# schematic.net
KiCad netlist of a schematic drawn in EAGLE
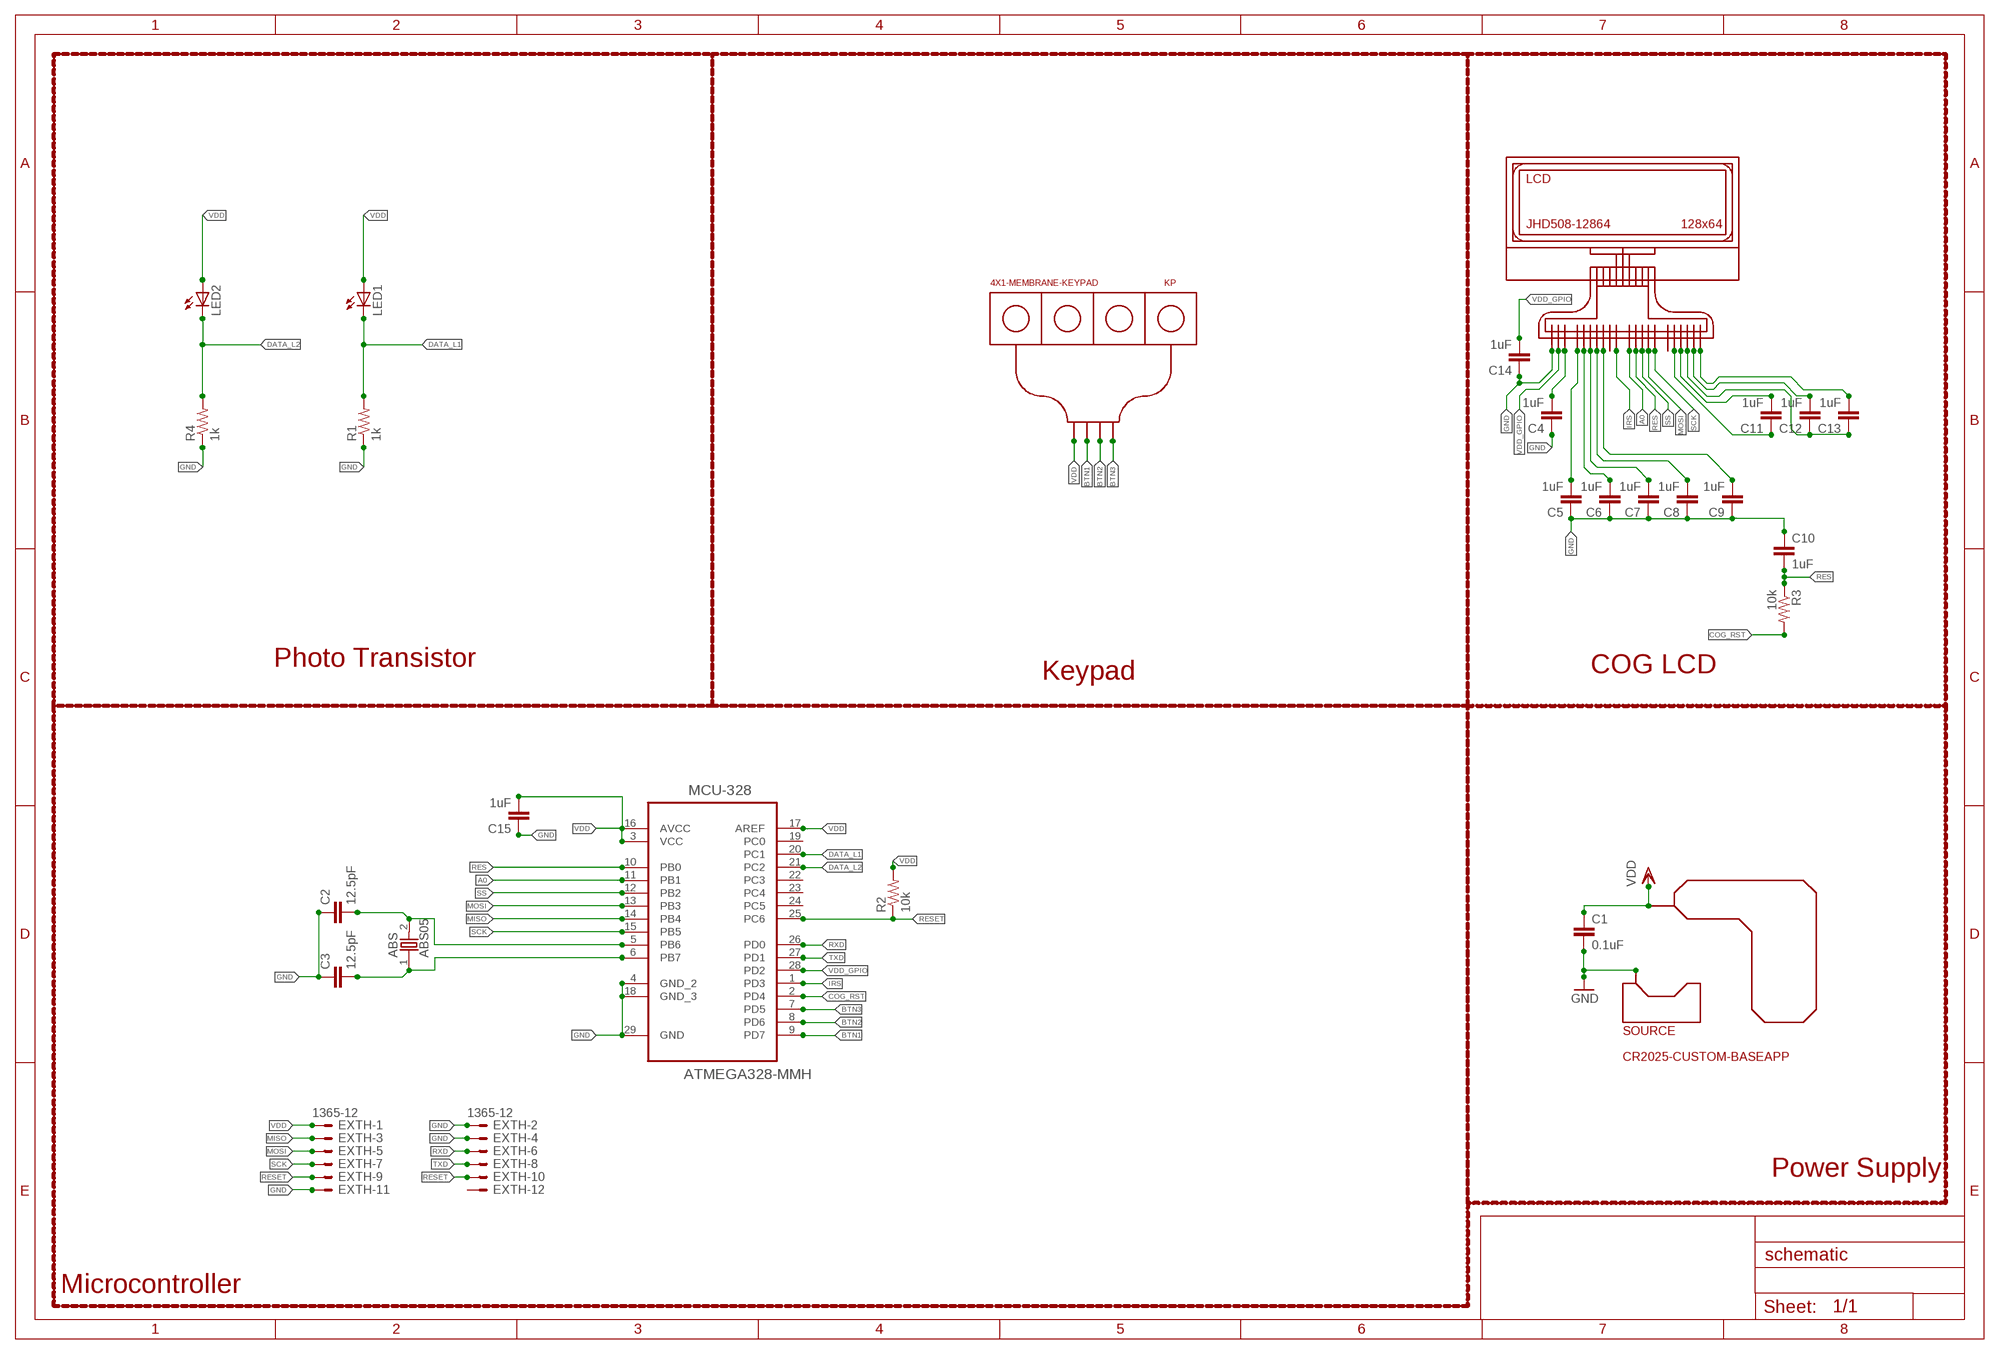
[diagram p0: schematic, sheet 1]

(export (version "E")
  (design (tool "Eeschema 10.0.6"))
  (components
    (comp (ref "ABS")
      (value "ABS05")
      (footprint "eagle-import:ABS05")
      (libsource (lib "eagle-import") (part "ABS05"))
    )
    (comp (ref "C1")
      (value "0.1uF")
      (footprint "eagle-import:0402-CAP")
      (libsource (lib "eagle-import") (part "CAP0402-CAP"))
    )
    (comp (ref "C2")
      (value "12.5pF")
      (footprint "eagle-import:0402-CAP")
      (libsource (lib "eagle-import") (part "CAP0402-CAP"))
    )
    (comp (ref "C3")
      (value "12.5pF")
      (footprint "eagle-import:0402-CAP")
      (libsource (lib "eagle-import") (part "CAP0402-CAP"))
    )
    (comp (ref "C4")
      (value "1uF")
      (footprint "eagle-import:0402-CAP")
      (libsource (lib "eagle-import") (part "CAP0402-CAP"))
    )
    (comp (ref "C5")
      (value "1uF")
      (footprint "eagle-import:0402-CAP")
      (libsource (lib "eagle-import") (part "CAP0402-CAP"))
    )
    (comp (ref "C6")
      (value "1uF")
      (footprint "eagle-import:0402-CAP")
      (libsource (lib "eagle-import") (part "CAP0402-CAP"))
    )
    (comp (ref "C7")
      (value "1uF")
      (footprint "eagle-import:0402-CAP")
      (libsource (lib "eagle-import") (part "CAP0402-CAP"))
    )
    (comp (ref "C8")
      (value "1uF")
      (footprint "eagle-import:0402-CAP")
      (libsource (lib "eagle-import") (part "CAP0402-CAP"))
    )
    (comp (ref "C9")
      (value "1uF")
      (footprint "eagle-import:0402-CAP")
      (libsource (lib "eagle-import") (part "CAP0402-CAP"))
    )
    (comp (ref "C10")
      (value "1uF")
      (footprint "eagle-import:0402-CAP")
      (libsource (lib "eagle-import") (part "CAP0402-CAP"))
    )
    (comp (ref "C11")
      (value "1uF")
      (footprint "eagle-import:0402-CAP")
      (libsource (lib "eagle-import") (part "CAP0402-CAP"))
    )
    (comp (ref "C12")
      (value "1uF")
      (footprint "eagle-import:0402-CAP")
      (libsource (lib "eagle-import") (part "CAP0402-CAP"))
    )
    (comp (ref "C13")
      (value "1uF")
      (footprint "eagle-import:0402-CAP")
      (libsource (lib "eagle-import") (part "CAP0402-CAP"))
    )
    (comp (ref "C14")
      (value "1uF")
      (footprint "eagle-import:0402-CAP")
      (libsource (lib "eagle-import") (part "CAP0402-CAP"))
    )
    (comp (ref "C15")
      (value "1uF")
      (footprint "eagle-import:0402-CAP")
      (libsource (lib "eagle-import") (part "CAP0402-CAP"))
    )
    (comp (ref "EXTH")
      (value "1365-12")
      (footprint "eagle-import:1365-12")
      (libsource (lib "eagle-import") (part "1365-12"))
    )
    (comp (ref "KP")
      (value "4X1-MEMBRANE-KEYPAD")
      (footprint "eagle-import:4X1-MEMBRANE-KEYPAD")
      (libsource (lib "eagle-import") (part "4X1-MEMBRANE-KEYPAD"))
    )
    (comp (ref "LCD")
      (value "JHD508-12864")
      (footprint "eagle-import:FSTN")
      (libsource (lib "eagle-import") (part "JHD508-12864"))
    )
    (comp (ref "LED1")
      (value "LEDCHIP-LED0805")
      (footprint "eagle-import:CHIP-LED0805")
      (libsource (lib "eagle-import") (part "LEDCHIP-LED0805"))
    )
    (comp (ref "LED2")
      (value "LEDCHIP-LED0805")
      (footprint "eagle-import:CHIP-LED0805")
      (libsource (lib "eagle-import") (part "LEDCHIP-LED0805"))
    )
    (comp (ref "MCU-328")
      (value "ATMEGA328-MMH")
      (footprint "eagle-import:QFN45P400X400X100-29N")
      (libsource (lib "eagle-import") (part "ATMEGA328-MMH"))
    )
    (comp (ref "R1")
      (value "1k")
      (footprint "eagle-import:0402-RES")
      (libsource (lib "eagle-import") (part "RESISTOR0402-RES"))
    )
    (comp (ref "R2")
      (value "10k")
      (footprint "eagle-import:0402-RES")
      (libsource (lib "eagle-import") (part "RESISTOR0402-RES"))
    )
    (comp (ref "R3")
      (value "10k")
      (footprint "eagle-import:0402-RES")
      (libsource (lib "eagle-import") (part "RESISTOR0402-RES"))
    )
    (comp (ref "R4")
      (value "1k")
      (footprint "eagle-import:0402-RES")
      (libsource (lib "eagle-import") (part "RESISTOR0402-RES"))
    )
    (comp (ref "SOURCE")
      (value "CR2025-CUSTOM-BASEAPP")
      (footprint "eagle-import:CR2025-CUSTOM-BASEAPP")
      (libsource (lib "eagle-import") (part "CR2025-CUSTOM-BASEAPP"))
    )
  )
  (nets
    (net (code "1") (name "A0") (class "Default")
      (node (ref "LCD") (pin "P$19") (pinfunction "A0_P$19") (pintype "bidirectional"))
      (node (ref "MCU-328") (pin "11") (pinfunction "PB1_11") (pintype "bidirectional"))
    )
    (net (code "2") (name "BTN1") (class "Default")
      (node (ref "KP") (pin "P$2") (pinfunction "P$2_P$2") (pintype "bidirectional"))
      (node (ref "MCU-328") (pin "9") (pinfunction "PD7_9") (pintype "bidirectional"))
    )
    (net (code "3") (name "BTN2") (class "Default")
      (node (ref "KP") (pin "P$3") (pinfunction "P$3_P$3") (pintype "bidirectional"))
      (node (ref "MCU-328") (pin "8") (pinfunction "PD6_8") (pintype "bidirectional"))
    )
    (net (code "4") (name "BTN3") (class "Default")
      (node (ref "KP") (pin "P$4") (pinfunction "P$4_P$4") (pintype "bidirectional"))
      (node (ref "MCU-328") (pin "7") (pinfunction "PD5_7") (pintype "bidirectional"))
    )
    (net (code "5") (name "COG_RST") (class "Default")
      (node (ref "MCU-328") (pin "2") (pinfunction "PD4_2") (pintype "bidirectional"))
      (node (ref "R3") (pin "2") (pinfunction "2_2") (pintype "passive"))
    )
    (net (code "6") (name "DATA_L1") (class "Default")
      (node (ref "LED1") (pin "C") (pinfunction "C_C") (pintype "passive"))
      (node (ref "MCU-328") (pin "20") (pinfunction "PC1_20") (pintype "bidirectional"))
      (node (ref "R1") (pin "2") (pinfunction "2_2") (pintype "passive"))
    )
    (net (code "7") (name "DATA_L2") (class "Default")
      (node (ref "LED2") (pin "C") (pinfunction "C_C") (pintype "passive"))
      (node (ref "MCU-328") (pin "21") (pinfunction "PC2_21") (pintype "bidirectional"))
      (node (ref "R4") (pin "2") (pinfunction "2_2") (pintype "passive"))
    )
    (net (code "8") (name "GND") (class "Default")
      (node (ref "C1") (pin "2") (pinfunction "2_2") (pintype "passive"))
      (node (ref "C10") (pin "1") (pinfunction "1_1") (pintype "passive"))
      (node (ref "C14") (pin "1") (pinfunction "1_1") (pintype "passive"))
      (node (ref "C15") (pin "1") (pinfunction "1_1") (pintype "passive"))
      (node (ref "C2") (pin "1") (pinfunction "1_1") (pintype "passive"))
      (node (ref "C3") (pin "1") (pinfunction "1_1") (pintype "passive"))
      (node (ref "C4") (pin "1") (pinfunction "1_1") (pintype "passive"))
      (node (ref "C5") (pin "1") (pinfunction "1_1") (pintype "passive"))
      (node (ref "C6") (pin "1") (pinfunction "1_1") (pintype "passive"))
      (node (ref "C7") (pin "1") (pinfunction "1_1") (pintype "passive"))
      (node (ref "C8") (pin "1") (pinfunction "1_1") (pintype "passive"))
      (node (ref "C9") (pin "1") (pinfunction "1_1") (pintype "passive"))
      (node (ref "EXTH") (pin "11") (pinfunction "S_11") (pintype "passive"))
      (node (ref "EXTH") (pin "2") (pinfunction "S_2") (pintype "passive"))
      (node (ref "EXTH") (pin "4") (pinfunction "S_4") (pintype "passive"))
      (node (ref "LCD") (pin "P$15") (pinfunction "GND_P$15") (pintype "bidirectional"))
      (node (ref "MCU-328") (pin "18") (pinfunction "GND_3_18") (pintype "power_in"))
      (node (ref "MCU-328") (pin "29") (pinfunction "GND_29") (pintype "power_in"))
      (node (ref "MCU-328") (pin "4") (pinfunction "GND_2_4") (pintype "power_in"))
      (node (ref "R1") (pin "1") (pinfunction "1_1") (pintype "passive"))
      (node (ref "R4") (pin "1") (pinfunction "1_1") (pintype "passive"))
      (node (ref "SOURCE") (pin "1") (pinfunction "GND_1") (pintype "bidirectional"))
    )
    (net (code "9") (name "IRS") (class "Default")
      (node (ref "LCD") (pin "P$1") (pinfunction "IRS_P$1") (pintype "bidirectional"))
      (node (ref "MCU-328") (pin "1") (pinfunction "PD3_1") (pintype "bidirectional"))
    )
    (net (code "10") (name "MISO") (class "Default")
      (node (ref "EXTH") (pin "3") (pinfunction "S_3") (pintype "passive"))
      (node (ref "MCU-328") (pin "14") (pinfunction "PB4_14") (pintype "bidirectional"))
    )
    (net (code "11") (name "MOSI") (class "Default")
      (node (ref "EXTH") (pin "5") (pinfunction "S_5") (pintype "passive"))
      (node (ref "LCD") (pin "P$17") (pinfunction "SI_P$17") (pintype "bidirectional"))
      (node (ref "MCU-328") (pin "13") (pinfunction "PB3_13") (pintype "bidirectional"))
    )
    (net (code "12") (name "Net-(LCD-CAP1N)") (class "Default")
      (node (ref "C12") (pin "1") (pinfunction "1_1") (pintype "passive"))
      (node (ref "C13") (pin "1") (pinfunction "1_1") (pintype "passive"))
      (node (ref "LCD") (pin "P$11") (pinfunction "CAP1N_P$11") (pintype "bidirectional"))
    )
    (net (code "13") (name "Net-(LCD-CAP1P)") (class "Default")
      (node (ref "C12") (pin "2") (pinfunction "2_2") (pintype "passive"))
      (node (ref "LCD") (pin "P$12") (pinfunction "CAP1P_P$12") (pintype "bidirectional"))
    )
    (net (code "14") (name "Net-(LCD-CAP2N)") (class "Default")
      (node (ref "C11") (pin "2") (pinfunction "2_2") (pintype "passive"))
      (node (ref "LCD") (pin "P$10") (pinfunction "CAP2N_P$10") (pintype "bidirectional"))
    )
    (net (code "15") (name "Net-(LCD-CAP2P)") (class "Default")
      (node (ref "C11") (pin "1") (pinfunction "1_1") (pintype "passive"))
      (node (ref "LCD") (pin "P$9") (pinfunction "CAP2P_P$9") (pintype "bidirectional"))
    )
    (net (code "16") (name "Net-(LCD-CAP3N)") (class "Default")
      (node (ref "C13") (pin "2") (pinfunction "2_2") (pintype "passive"))
      (node (ref "LCD") (pin "P$13") (pinfunction "CAP3N_P$13") (pintype "bidirectional"))
    )
    (net (code "17") (name "Net-(LCD-V1)") (class "Default")
      (node (ref "C5") (pin "2") (pinfunction "2_2") (pintype "passive"))
      (node (ref "LCD") (pin "P$7") (pinfunction "V1_P$7") (pintype "bidirectional"))
    )
    (net (code "18") (name "Net-(LCD-V2)") (class "Default")
      (node (ref "C6") (pin "2") (pinfunction "2_2") (pintype "passive"))
      (node (ref "LCD") (pin "P$6") (pinfunction "V2_P$6") (pintype "bidirectional"))
    )
    (net (code "19") (name "Net-(LCD-V3)") (class "Default")
      (node (ref "C7") (pin "2") (pinfunction "2_2") (pintype "passive"))
      (node (ref "LCD") (pin "P$5") (pinfunction "V3_P$5") (pintype "bidirectional"))
    )
    (net (code "20") (name "Net-(LCD-V4)") (class "Default")
      (node (ref "C8") (pin "2") (pinfunction "2_2") (pintype "passive"))
      (node (ref "LCD") (pin "P$4") (pinfunction "V4_P$4") (pintype "bidirectional"))
    )
    (net (code "21") (name "Net-(LCD-V5)") (class "Default")
      (node (ref "C9") (pin "2") (pinfunction "2_2") (pintype "passive"))
      (node (ref "LCD") (pin "P$3") (pinfunction "V5_P$3") (pintype "bidirectional"))
    )
    (net (code "22") (name "Net-(LCD-VOUT)") (class "Default")
      (node (ref "C4") (pin "2") (pinfunction "2_2") (pintype "passive"))
      (node (ref "LCD") (pin "P$14") (pinfunction "VOUT_P$14") (pintype "bidirectional"))
    )
    (net (code "23") (name "Net-(MCU-328-PB6)") (class "Default")
      (node (ref "ABS") (pin "2") (pinfunction "2_2") (pintype "passive"))
      (node (ref "C2") (pin "2") (pinfunction "2_2") (pintype "passive"))
      (node (ref "MCU-328") (pin "5") (pinfunction "PB6_5") (pintype "bidirectional"))
    )
    (net (code "24") (name "Net-(MCU-328-PB7)") (class "Default")
      (node (ref "ABS") (pin "1") (pinfunction "1_1") (pintype "passive"))
      (node (ref "C3") (pin "2") (pinfunction "2_2") (pintype "passive"))
      (node (ref "MCU-328") (pin "6") (pinfunction "PB7_6") (pintype "bidirectional"))
    )
    (net (code "25") (name "RES") (class "Default")
      (node (ref "C10") (pin "2") (pinfunction "2_2") (pintype "passive"))
      (node (ref "LCD") (pin "P$20") (pinfunction "/RES_P$20") (pintype "bidirectional"))
      (node (ref "MCU-328") (pin "10") (pinfunction "PB0_10") (pintype "bidirectional"))
      (node (ref "R3") (pin "1") (pinfunction "1_1") (pintype "passive"))
    )
    (net (code "26") (name "RESET") (class "Default")
      (node (ref "EXTH") (pin "10") (pinfunction "S_10") (pintype "passive"))
      (node (ref "EXTH") (pin "9") (pinfunction "S_9") (pintype "passive"))
      (node (ref "MCU-328") (pin "25") (pinfunction "PC6_25") (pintype "bidirectional"))
      (node (ref "R2") (pin "1") (pinfunction "1_1") (pintype "passive"))
    )
    (net (code "27") (name "RXD") (class "Default")
      (node (ref "EXTH") (pin "6") (pinfunction "S_6") (pintype "passive"))
      (node (ref "MCU-328") (pin "26") (pinfunction "PD0_26") (pintype "bidirectional"))
    )
    (net (code "28") (name "SCK") (class "Default")
      (node (ref "EXTH") (pin "7") (pinfunction "S_7") (pintype "passive"))
      (node (ref "LCD") (pin "P$18") (pinfunction "SCL_P$18") (pintype "bidirectional"))
      (node (ref "MCU-328") (pin "15") (pinfunction "PB5_15") (pintype "bidirectional"))
    )
    (net (code "29") (name "SS") (class "Default")
      (node (ref "LCD") (pin "P$21") (pinfunction "/CS1_P$21") (pintype "bidirectional"))
      (node (ref "MCU-328") (pin "12") (pinfunction "PB2_12") (pintype "bidirectional"))
    )
    (net (code "30") (name "TXD") (class "Default")
      (node (ref "EXTH") (pin "8") (pinfunction "S_8") (pintype "passive"))
      (node (ref "MCU-328") (pin "27") (pinfunction "PD1_27") (pintype "bidirectional"))
    )
    (net (code "31") (name "VDD") (class "Default")
      (node (ref "C1") (pin "1") (pinfunction "1_1") (pintype "passive"))
      (node (ref "C15") (pin "2") (pinfunction "2_2") (pintype "passive"))
      (node (ref "EXTH") (pin "1") (pinfunction "S_1") (pintype "passive"))
      (node (ref "KP") (pin "P$1") (pinfunction "P$1_P$1") (pintype "bidirectional"))
      (node (ref "LED1") (pin "A") (pinfunction "A_A") (pintype "passive"))
      (node (ref "LED2") (pin "A") (pinfunction "A_A") (pintype "passive"))
      (node (ref "MCU-328") (pin "16") (pinfunction "AVCC_16") (pintype "power_in"))
      (node (ref "MCU-328") (pin "17") (pinfunction "AREF_17") (pintype "passive"))
      (node (ref "MCU-328") (pin "3") (pinfunction "VCC_3") (pintype "power_in"))
      (node (ref "R2") (pin "2") (pinfunction "2_2") (pintype "passive"))
      (node (ref "SOURCE") (pin "2") (pinfunction "VDD_2") (pintype "bidirectional"))
    )
    (net (code "32") (name "VDD_GPIO") (class "Default")
      (node (ref "C14") (pin "2") (pinfunction "2_2") (pintype "passive"))
      (node (ref "LCD") (pin "P$16") (pinfunction "VDD_P$16") (pintype "bidirectional"))
      (node (ref "MCU-328") (pin "28") (pinfunction "PD2_28") (pintype "bidirectional"))
    )
    (net (code "33") (name "unconnected-(EXTHD-S-Pad12)") (class "Default")
      (node (ref "EXTH") (pin "12") (pinfunction "S_12") (pintype "passive"))
    )
    (net (code "34") (name "unconnected-(LCD-CAP4N-PadP$8)") (class "Default")
      (node (ref "LCD") (pin "P$8") (pinfunction "CAP4N_P$8") (pintype "bidirectional"))
    )
    (net (code "35") (name "unconnected-(LCD-VR-PadP$2)") (class "Default")
      (node (ref "LCD") (pin "P$2") (pinfunction "VR_P$2") (pintype "bidirectional"))
    )
    (net (code "36") (name "unconnected-(MCU-328-PC0-Pad19)") (class "Default")
      (node (ref "MCU-328") (pin "19") (pinfunction "PC0_19") (pintype "bidirectional"))
    )
    (net (code "37") (name "unconnected-(MCU-328-PC3-Pad22)") (class "Default")
      (node (ref "MCU-328") (pin "22") (pinfunction "PC3_22") (pintype "bidirectional"))
    )
    (net (code "38") (name "unconnected-(MCU-328-PC4-Pad23)") (class "Default")
      (node (ref "MCU-328") (pin "23") (pinfunction "PC4_23") (pintype "bidirectional"))
    )
    (net (code "39") (name "unconnected-(MCU-328-PC5-Pad24)") (class "Default")
      (node (ref "MCU-328") (pin "24") (pinfunction "PC5_24") (pintype "bidirectional"))
    )
  )
)
